# fab-speakers-noss-edits-diff-ended-input.net
KiCad netlist of a schematic drawn in EAGLE
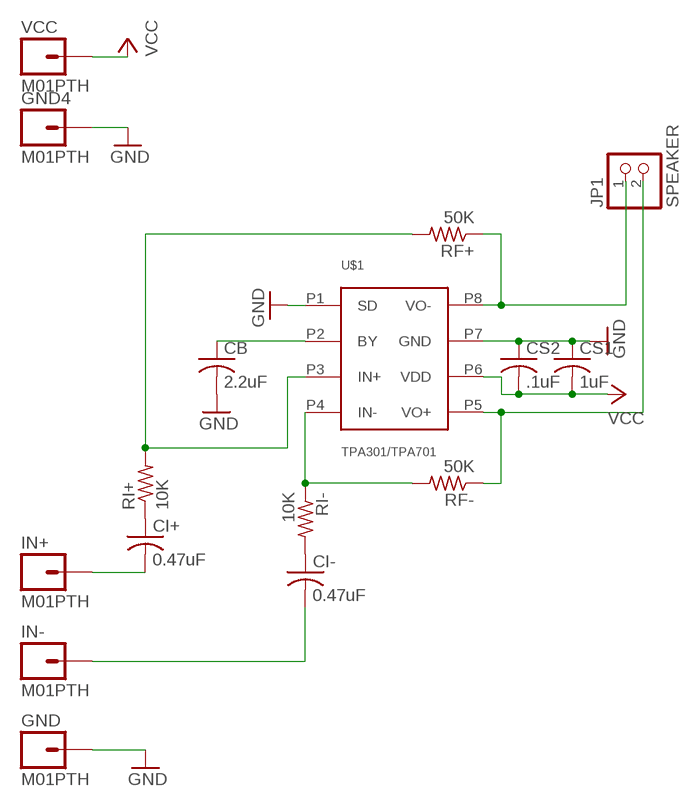
[diagram p0: schematic, sheet 1]

(export (version "E")
  (design (tool "Eeschema 10.0.6"))
  (components
    (comp (ref "CB")
      (value "2.2uF")
      (footprint "eagle-import:C0603")
      (libsource (lib "eagle-import") (part "C-USC0603"))
    )
    (comp (ref "CI+")
      (value "0.47uF")
      (footprint "eagle-import:C0603")
      (libsource (lib "eagle-import") (part "C-USC0603"))
    )
    (comp (ref "CI-")
      (value "0.47uF")
      (footprint "eagle-import:C0603")
      (libsource (lib "eagle-import") (part "C-USC0603"))
    )
    (comp (ref "CS1")
      (value "1uF")
      (footprint "eagle-import:C0603")
      (libsource (lib "eagle-import") (part "C-USC0603"))
    )
    (comp (ref "CS2")
      (value ".1uF")
      (footprint "eagle-import:C0603")
      (libsource (lib "eagle-import") (part "C-USC0603"))
    )
    (comp (ref "GND")
      (value "M01PTH")
      (footprint "eagle-import:1X01")
      (libsource (lib "eagle-import") (part "M01PTH"))
    )
    (comp (ref "GND4")
      (value "M01PTH")
      (footprint "eagle-import:1X01")
      (libsource (lib "eagle-import") (part "M01PTH"))
    )
    (comp (ref "IN+")
      (value "M01PTH")
      (footprint "eagle-import:1X01")
      (libsource (lib "eagle-import") (part "M01PTH"))
    )
    (comp (ref "IN-")
      (value "M01PTH")
      (footprint "eagle-import:1X01")
      (libsource (lib "eagle-import") (part "M01PTH"))
    )
    (comp (ref "JP1")
      (value "SPEAKER")
      (footprint "eagle-import:1X02")
      (libsource (lib "eagle-import") (part "PINHD-1X2"))
    )
    (comp (ref "RF+")
      (value "50K")
      (footprint "eagle-import:R0603")
      (libsource (lib "eagle-import") (part "R-US_R0603"))
    )
    (comp (ref "RF-")
      (value "50K")
      (footprint "eagle-import:R0603")
      (libsource (lib "eagle-import") (part "R-US_R0603"))
    )
    (comp (ref "RI+")
      (value "10K")
      (footprint "eagle-import:R0603")
      (libsource (lib "eagle-import") (part "R-US_R0603"))
    )
    (comp (ref "RI-")
      (value "10K")
      (footprint "eagle-import:R0603")
      (libsource (lib "eagle-import") (part "R-US_R0603"))
    )
    (comp (ref "U$1")
      (value "TPA301/TPA701")
      (footprint "eagle-import:SOIC8")
      (libsource (lib "eagle-import") (part "TPA301/TPA701"))
    )
    (comp (ref "VCC")
      (value "M01PTH")
      (footprint "eagle-import:1X01")
      (libsource (lib "eagle-import") (part "M01PTH"))
    )
  )
  (nets
    (net (code "1") (name "GND") (class "Default")
      (node (ref "CB") (pin "2") (pinfunction "2_2") (pintype "passive"))
      (node (ref "CS1") (pin "1") (pinfunction "1_1") (pintype "passive"))
      (node (ref "CS2") (pin "1") (pinfunction "1_1") (pintype "passive"))
      (node (ref "GND") (pin "1") (pinfunction "1_1") (pintype "passive"))
      (node (ref "GND4") (pin "1") (pinfunction "1_1") (pintype "passive"))
      (node (ref "U$1") (pin "P1") (pinfunction "SD_P1") (pintype "bidirectional"))
      (node (ref "U$1") (pin "P7") (pinfunction "GND_P7") (pintype "bidirectional"))
    )
    (net (code "2") (name "Net-(CI+-Pad1)") (class "Default")
      (node (ref "CI+") (pin "1") (pinfunction "1_1") (pintype "passive"))
      (node (ref "RI+") (pin "1") (pinfunction "1_1") (pintype "passive"))
    )
    (net (code "3") (name "Net-(CI+-Pad2)") (class "Default")
      (node (ref "CI+") (pin "2") (pinfunction "2_2") (pintype "passive"))
      (node (ref "IN+") (pin "1") (pinfunction "1_1") (pintype "passive"))
    )
    (net (code "4") (name "Net-(CI--Pad1)") (class "Default")
      (node (ref "CI-") (pin "1") (pinfunction "1_1") (pintype "passive"))
      (node (ref "RI-") (pin "2") (pinfunction "2_2") (pintype "passive"))
    )
    (net (code "5") (name "Net-(CI--Pad2)") (class "Default")
      (node (ref "CI-") (pin "2") (pinfunction "2_2") (pintype "passive"))
      (node (ref "IN-") (pin "1") (pinfunction "1_1") (pintype "passive"))
    )
    (net (code "6") (name "Net-(U$1-BY)") (class "Default")
      (node (ref "CB") (pin "1") (pinfunction "1_1") (pintype "passive"))
      (node (ref "U$1") (pin "P2") (pinfunction "BY_P2") (pintype "bidirectional"))
    )
    (net (code "7") (name "Net-(U$1-IN+)") (class "Default")
      (node (ref "RF+") (pin "2") (pinfunction "2_2") (pintype "passive"))
      (node (ref "RI+") (pin "2") (pinfunction "2_2") (pintype "passive"))
      (node (ref "U$1") (pin "P3") (pinfunction "IN+_P3") (pintype "bidirectional"))
    )
    (net (code "8") (name "Net-(U$1-IN-)") (class "Default")
      (node (ref "RF-") (pin "2") (pinfunction "2_2") (pintype "passive"))
      (node (ref "RI-") (pin "1") (pinfunction "1_1") (pintype "passive"))
      (node (ref "U$1") (pin "P4") (pinfunction "IN-_P4") (pintype "bidirectional"))
    )
    (net (code "9") (name "Net-(U$1-VO+)") (class "Default")
      (node (ref "JP1") (pin "2") (pinfunction "2_2") (pintype "passive"))
      (node (ref "RF-") (pin "1") (pinfunction "1_1") (pintype "passive"))
      (node (ref "U$1") (pin "P5") (pinfunction "VO+_P5") (pintype "bidirectional"))
    )
    (net (code "10") (name "Net-(U$1-VO-)") (class "Default")
      (node (ref "JP1") (pin "1") (pinfunction "1_1") (pintype "passive"))
      (node (ref "RF+") (pin "1") (pinfunction "1_1") (pintype "passive"))
      (node (ref "U$1") (pin "P8") (pinfunction "VO-_P8") (pintype "bidirectional"))
    )
    (net (code "11") (name "VCC") (class "Default")
      (node (ref "CS1") (pin "2") (pinfunction "2_2") (pintype "passive"))
      (node (ref "CS2") (pin "2") (pinfunction "2_2") (pintype "passive"))
      (node (ref "U$1") (pin "P6") (pinfunction "VDD_P6") (pintype "bidirectional"))
      (node (ref "VCC") (pin "1") (pinfunction "1_1") (pintype "passive"))
    )
  )
)
